# LPCB281_-_DIR_RELAYS.net
KiCad netlist of a schematic drawn in Altium Designer
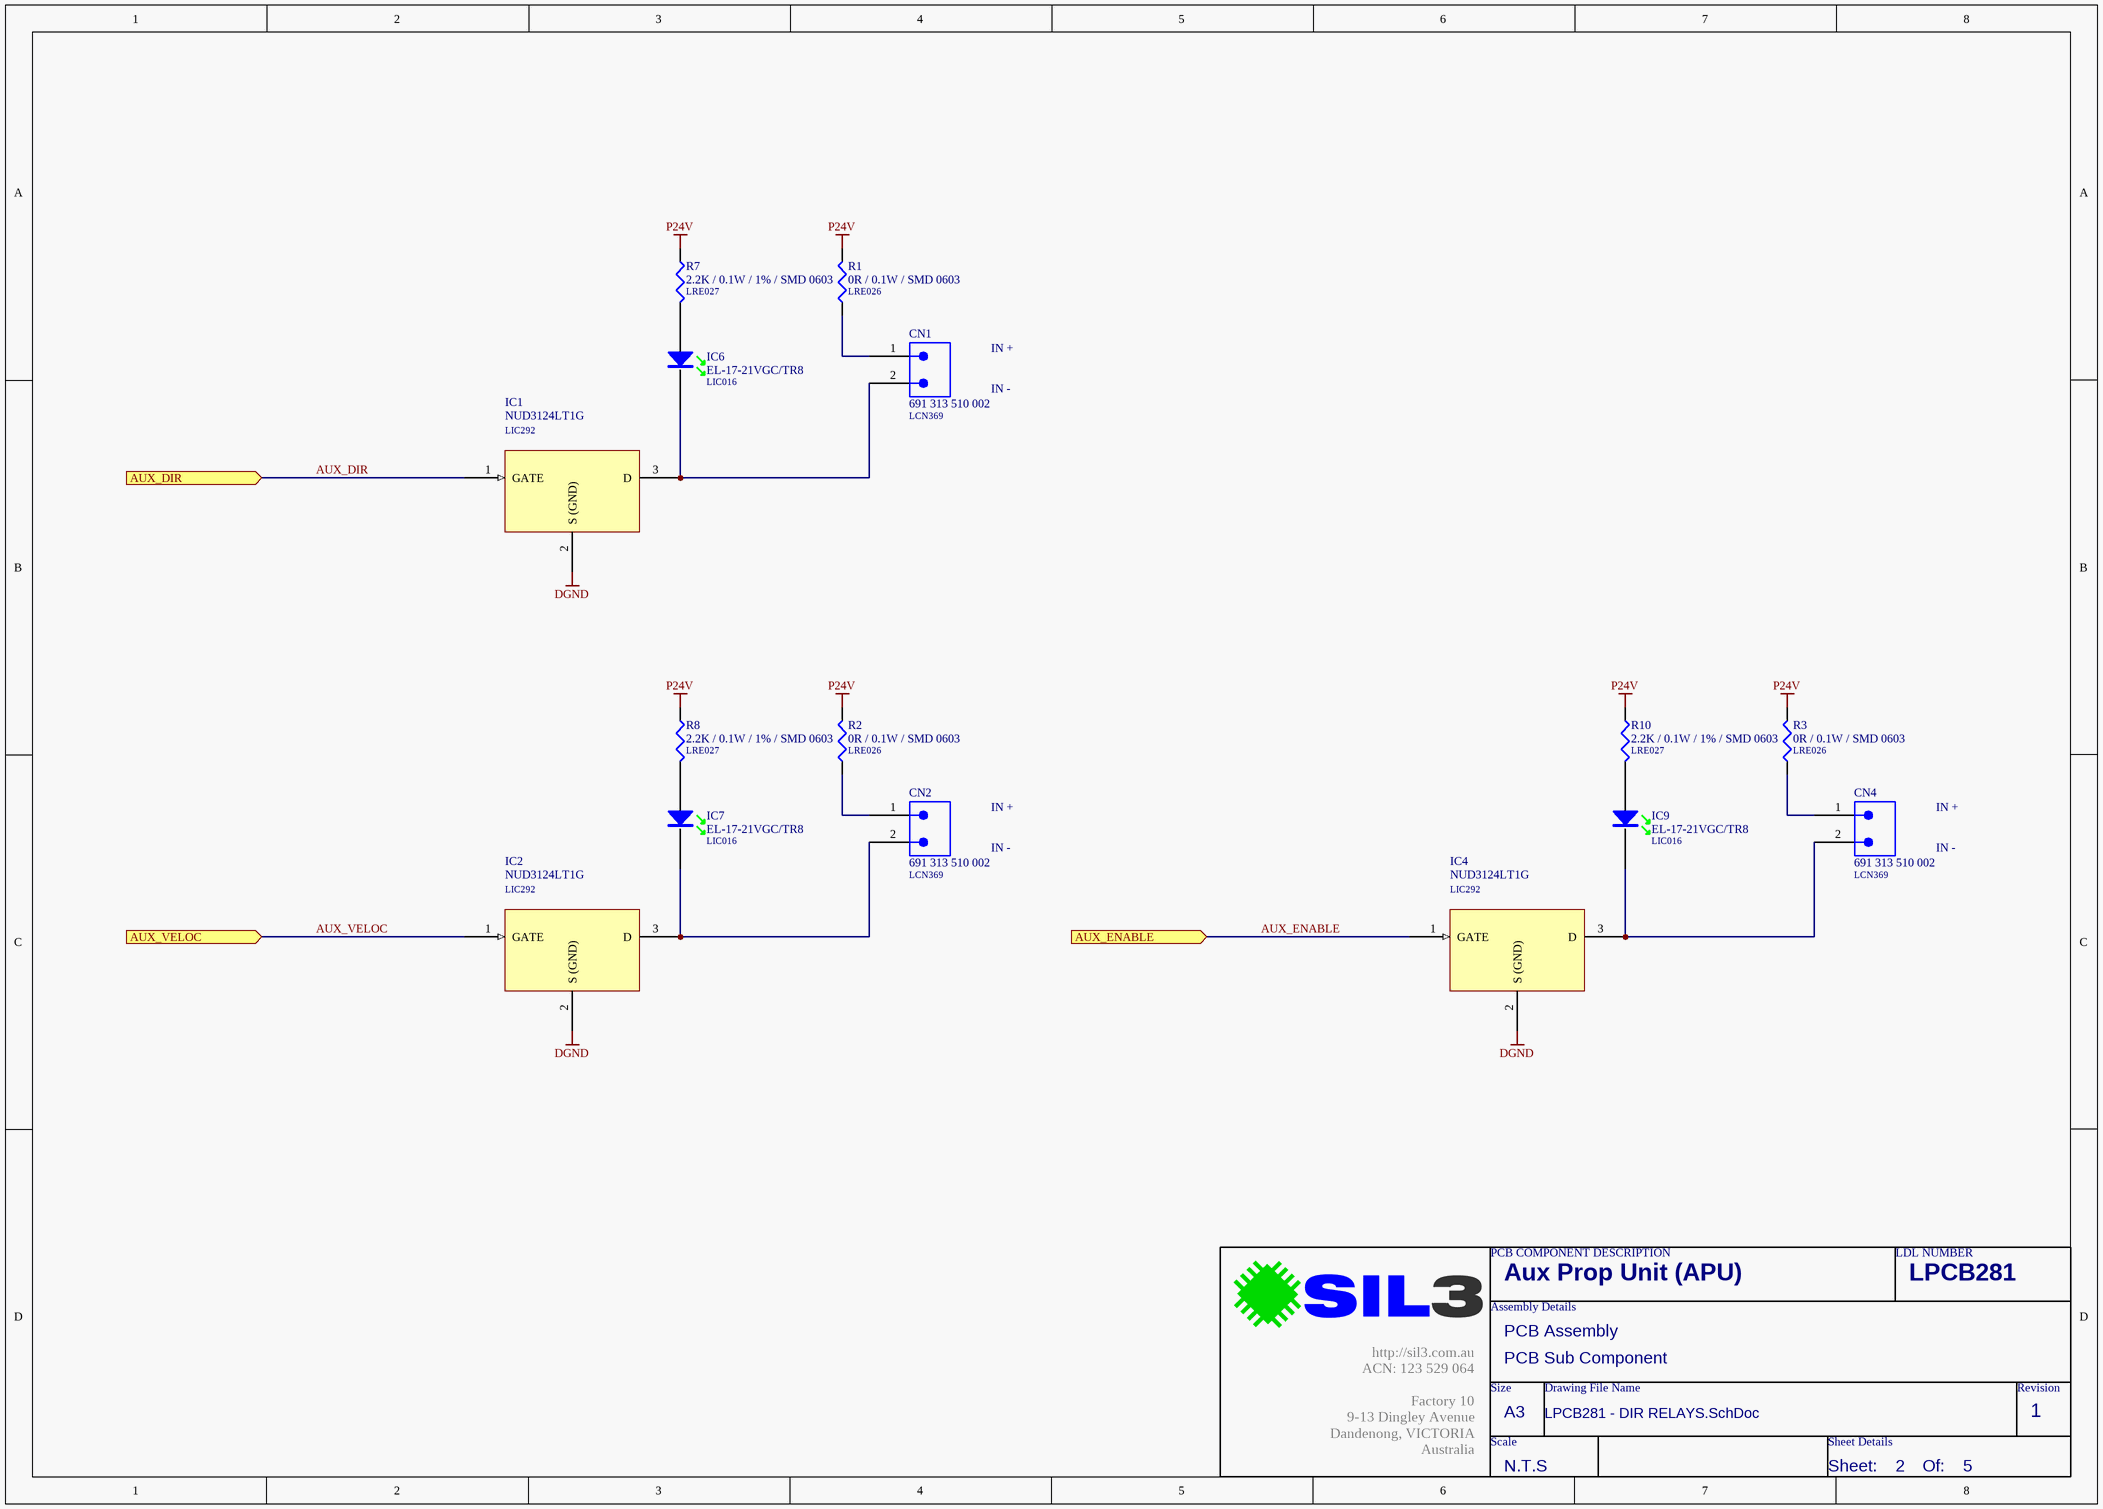
[diagram p0: LPCB281 - DIR RELAYS.SchDoc]

(export (version "E")
  (design (tool "Eeschema 10.0.6"))
  (components
    (comp (ref "CN1")
      (value "691 313 510 002")
      (footprint "691 313 510 002")
      (description "Connector, Pluggable Terminal Block, 5.08mm, 2 Way, PTH")
      (fields (field (name "LDL_NUMBER") "LCN369"))
      (libsource (lib "LDL_Connectors") (part "691 313 510 002"))
    )
    (comp (ref "CN2")
      (value "691 313 510 002")
      (footprint "691 313 510 002")
      (description "Connector, Pluggable Terminal Block, 5.08mm, 2 Way, PTH")
      (fields (field (name "LDL_NUMBER") "LCN369"))
      (libsource (lib "LDL_Connectors") (part "691 313 510 002"))
    )
    (comp (ref "CN4")
      (value "691 313 510 002")
      (footprint "691 313 510 002")
      (description "Connector, Pluggable Terminal Block, 5.08mm, 2 Way, PTH")
      (fields (field (name "LDL_NUMBER") "LCN369"))
      (libsource (lib "LDL_Connectors") (part "691 313 510 002"))
    )
    (comp (ref "IC1")
      (value "NUD3124LT1G")
      (footprint "LFP021__SOT23")
      (description "IC, Relay Driver, 28V Industrial, SMD SOT23 [LIC292]")
      (fields (field (name "LDL_NUMBER") "LIC292"))
      (libsource (lib "LDL_Semiconductors") (part "NUD3124LT1G"))
    )
    (comp (ref "IC2")
      (value "NUD3124LT1G")
      (footprint "LFP021__SOT23")
      (description "IC, Relay Driver, 28V Industrial, SMD SOT23 [LIC292]")
      (fields (field (name "LDL_NUMBER") "LIC292"))
      (libsource (lib "LDL_Semiconductors") (part "NUD3124LT1G"))
    )
    (comp (ref "IC4")
      (value "NUD3124LT1G")
      (footprint "LFP021__SOT23")
      (description "IC, Relay Driver, 28V Industrial, SMD SOT23 [LIC292]")
      (fields (field (name "LDL_NUMBER") "LIC292"))
      (libsource (lib "LDL_Semiconductors") (part "NUD3124LT1G"))
    )
    (comp (ref "IC6")
      (value "EL-17-21VGC/TR8")
      (footprint "CR2012-0805-LED")
      (description "LED, SMD, 0805 Green [LIC016]")
      (fields (field (name "LDL_NUMBER") "LIC016"))
      (libsource (lib "LDL_Semiconductors") (part "EL-17-21VGC/TR8"))
    )
    (comp (ref "IC7")
      (value "EL-17-21VGC/TR8")
      (footprint "CR2012-0805-LED")
      (description "LED, SMD, 0805 Green [LIC016]")
      (fields (field (name "LDL_NUMBER") "LIC016"))
      (libsource (lib "LDL_Semiconductors") (part "EL-17-21VGC/TR8"))
    )
    (comp (ref "IC9")
      (value "EL-17-21VGC/TR8")
      (footprint "CR2012-0805-LED")
      (description "LED, SMD, 0805 Green [LIC016]")
      (fields (field (name "LDL_NUMBER") "LIC016"))
      (libsource (lib "LDL_Semiconductors") (part "EL-17-21VGC/TR8"))
    )
    (comp (ref "R1")
      (value "0R / 0.1W / SMD 0603")
      (footprint "LFP020__CR1608-0603-IPC7351_B")
      (description "Resistor, Ceramic Chip, 0R, 0.1W, SMD 0603 [LRE026]")
      (fields (field (name "LDL_NUMBER") "LRE026"))
      (libsource (lib "LDL_Resistors") (part "0R / 0.1W / SMD 0603"))
    )
    (comp (ref "R2")
      (value "0R / 0.1W / SMD 0603")
      (footprint "LFP020__CR1608-0603-IPC7351_B")
      (description "Resistor, Ceramic Chip, 0R, 0.1W, SMD 0603 [LRE026]")
      (fields (field (name "LDL_NUMBER") "LRE026"))
      (libsource (lib "LDL_Resistors") (part "0R / 0.1W / SMD 0603"))
    )
    (comp (ref "R3")
      (value "0R / 0.1W / SMD 0603")
      (footprint "LFP020__CR1608-0603-IPC7351_B")
      (description "Resistor, Ceramic Chip, 0R, 0.1W, SMD 0603 [LRE026]")
      (fields (field (name "LDL_NUMBER") "LRE026"))
      (libsource (lib "LDL_Resistors") (part "0R / 0.1W / SMD 0603"))
    )
    (comp (ref "R7")
      (value "2.2K / 0.1W / 1% / SMD 0603")
      (footprint "LFP020__CR1608-0603-IPC7351_B")
      (description "Resistor, Ceramic Chip, 2.2K, 0.1W, 1%, SMD 0603 [LRE027]")
      (fields (field (name "LDL_NUMBER") "LRE027"))
      (libsource (lib "LDL_Resistors") (part "2.2K / 0.1W / 1% / SMD 0603"))
    )
    (comp (ref "R8")
      (value "2.2K / 0.1W / 1% / SMD 0603")
      (footprint "LFP020__CR1608-0603-IPC7351_B")
      (description "Resistor, Ceramic Chip, 2.2K, 0.1W, 1%, SMD 0603 [LRE027]")
      (fields (field (name "LDL_NUMBER") "LRE027"))
      (libsource (lib "LDL_Resistors") (part "2.2K / 0.1W / 1% / SMD 0603"))
    )
    (comp (ref "R10")
      (value "2.2K / 0.1W / 1% / SMD 0603")
      (footprint "LFP020__CR1608-0603-IPC7351_B")
      (description "Resistor, Ceramic Chip, 2.2K, 0.1W, 1%, SMD 0603 [LRE027]")
      (fields (field (name "LDL_NUMBER") "LRE027"))
      (libsource (lib "LDL_Resistors") (part "2.2K / 0.1W / 1% / SMD 0603"))
    )
  )
  (nets
    (net (code "1") (name "/AUX_DIR") (class "Default")
      (node (ref "IC1") (pin "1") (pinfunction "GATE_1") (pintype "input"))
    )
    (net (code "2") (name "/AUX_ENABLE") (class "Default")
      (node (ref "IC4") (pin "1") (pinfunction "GATE_1") (pintype "input"))
    )
    (net (code "3") (name "/AUX_VELOC") (class "Default")
      (node (ref "IC2") (pin "1") (pinfunction "GATE_1") (pintype "input"))
    )
    (net (code "4") (name "DGND") (class "Default")
      (node (ref "IC1") (pin "2") (pinfunction "S_(GND)_2") (pintype "passive"))
      (node (ref "IC2") (pin "2") (pinfunction "S_(GND)_2") (pintype "passive"))
      (node (ref "IC4") (pin "2") (pinfunction "S_(GND)_2") (pintype "passive"))
    )
    (net (code "5") (name "Net-(CN1-Pad1)") (class "Default")
      (node (ref "CN1") (pin "1") (pinfunction "1_1") (pintype "passive"))
      (node (ref "R1") (pin "1") (pintype "passive"))
    )
    (net (code "6") (name "Net-(CN2-Pad1)") (class "Default")
      (node (ref "CN2") (pin "1") (pinfunction "1_1") (pintype "passive"))
      (node (ref "R2") (pin "1") (pintype "passive"))
    )
    (net (code "7") (name "Net-(CN4-Pad1)") (class "Default")
      (node (ref "CN4") (pin "1") (pinfunction "1_1") (pintype "passive"))
      (node (ref "R3") (pin "1") (pintype "passive"))
    )
    (net (code "8") (name "Net-(IC1-D)") (class "Default")
      (node (ref "CN1") (pin "2") (pinfunction "2_2") (pintype "passive"))
      (node (ref "IC1") (pin "3") (pinfunction "D_3") (pintype "passive"))
      (node (ref "IC6") (pin "K") (pintype "passive"))
    )
    (net (code "9") (name "Net-(IC2-D)") (class "Default")
      (node (ref "CN2") (pin "2") (pinfunction "2_2") (pintype "passive"))
      (node (ref "IC2") (pin "3") (pinfunction "D_3") (pintype "passive"))
      (node (ref "IC7") (pin "K") (pintype "passive"))
    )
    (net (code "10") (name "Net-(IC4-D)") (class "Default")
      (node (ref "CN4") (pin "2") (pinfunction "2_2") (pintype "passive"))
      (node (ref "IC4") (pin "3") (pinfunction "D_3") (pintype "passive"))
      (node (ref "IC9") (pin "K") (pintype "passive"))
    )
    (net (code "11") (name "Net-(IC6-PadA)") (class "Default")
      (node (ref "IC6") (pin "A") (pintype "passive"))
      (node (ref "R7") (pin "2") (pintype "passive"))
    )
    (net (code "12") (name "Net-(IC7-PadA)") (class "Default")
      (node (ref "IC7") (pin "A") (pintype "passive"))
      (node (ref "R8") (pin "2") (pintype "passive"))
    )
    (net (code "13") (name "Net-(IC9-PadA)") (class "Default")
      (node (ref "IC9") (pin "A") (pintype "passive"))
      (node (ref "R10") (pin "2") (pintype "passive"))
    )
    (net (code "14") (name "P24V") (class "Default")
      (node (ref "R1") (pin "2") (pintype "passive"))
      (node (ref "R10") (pin "1") (pintype "passive"))
      (node (ref "R2") (pin "2") (pintype "passive"))
      (node (ref "R3") (pin "2") (pintype "passive"))
      (node (ref "R7") (pin "1") (pintype "passive"))
      (node (ref "R8") (pin "1") (pintype "passive"))
    )
  )
)
